# ConversorBUCK.net
KiCad netlist of a schematic drawn in EasyEDA Pro
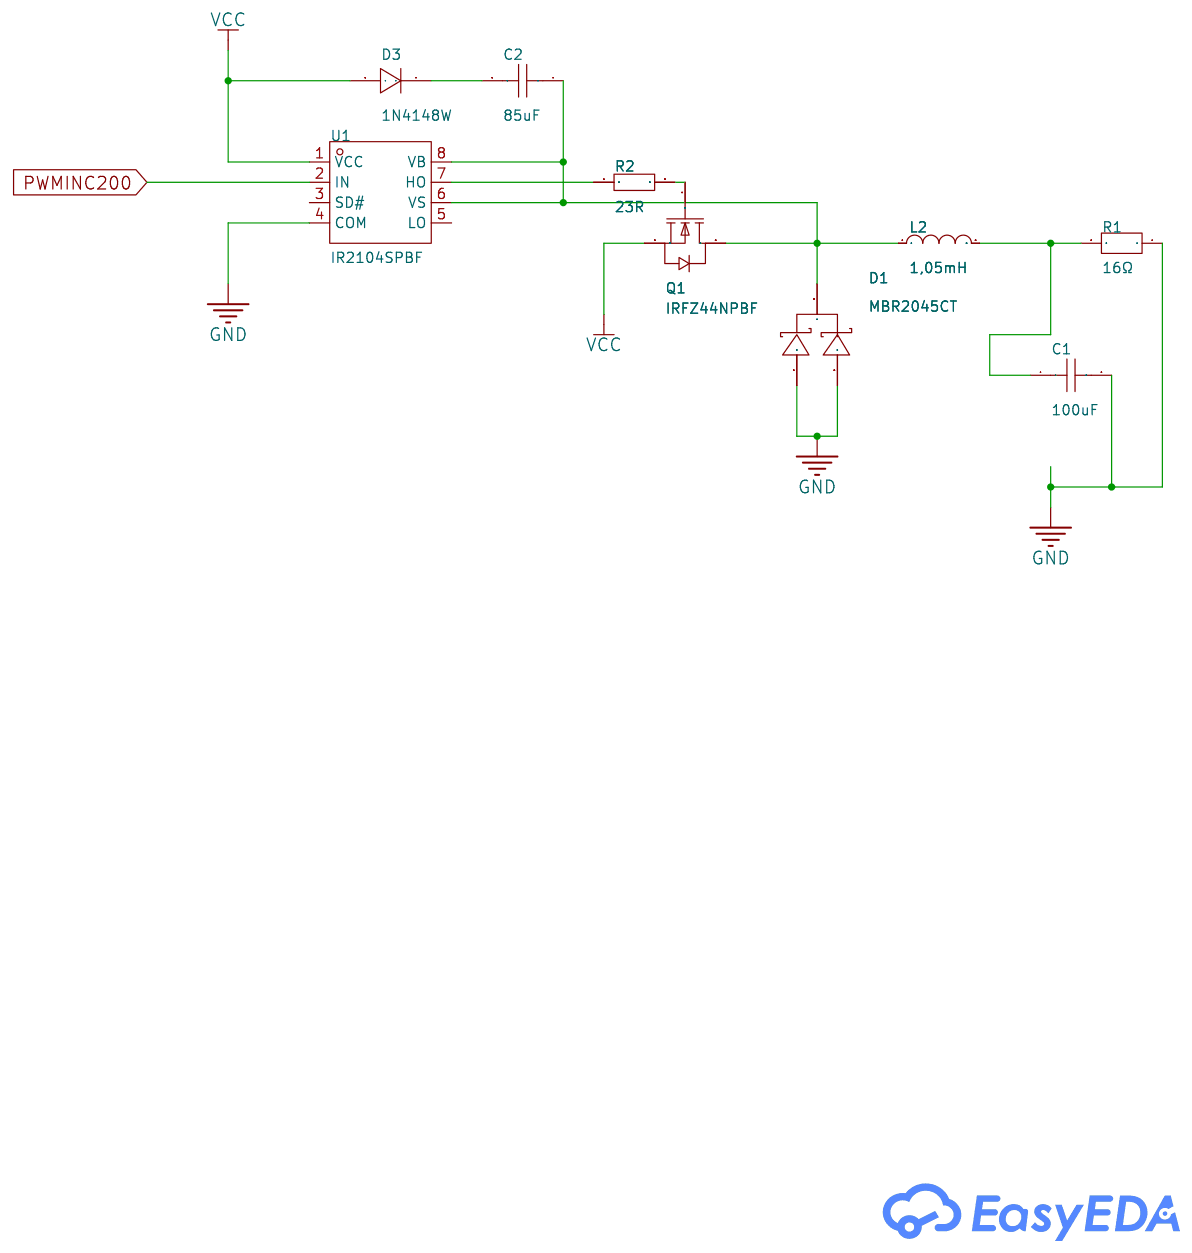
[diagram p0: schematic sheet]

(export (version "E")
  (design (tool "Eeschema 10.0.6"))
  (components
    (comp (ref "C1")
      (value "100uF")
      (footprint "easyedapro:C1210")
      (description "Capacitance:100uF Tolerance:±20% Tolerance:±20% Voltage Rating:6.3V Temperature Coefficient:X7T")
      (fields
        (field (name "Manufacturer Part") "CL32Z107MQV6PNE")
        (field (name "Manufacturer") "SAMSUNG(三星)")
      )
      (libsource (lib "easyedapro") (part "CL32Z107MQV6PNE"))
    )
    (comp (ref "C2")
      (value "85uF")
      (footprint "easyedapro:C0201")
      (libsource (lib "easyedapro") (part "CAP"))
    )
    (comp (ref "D1")
      (value "MBR2045CT")
      (footprint "easyedapro:TO-220AB-3_L10.4-W4.6-P2.54-T")
      (fields (field (name "Manufacturer") "PINGWEI(平伟)"))
      (libsource (lib "easyedapro") (part "MBR2045CT_C360496"))
    )
    (comp (ref "D3")
      (value "1N4148W")
      (footprint "easyedapro:SOD-123F_L2.7-W1.6-LS3.8-RD")
      (fields (field (name "Manufacturer") "ST(先科)"))
      (libsource (lib "easyedapro") (part "1N4148W_C81598"))
    )
    (comp (ref "L2")
      (value "1,05mH")
      (footprint "easyedapro:IND-SMD_L2.0-W1.2_PCT201210")
      (fields (field (name "Manufacturer Part") "PCT201210-1R0-M") (field (name "Manufacturer") "JIERR(捷而瑞)"))
      (libsource (lib "easyedapro") (part "PCT201210-1R0-M"))
    )
    (comp (ref "Q1")
      (value "IRFZ44NPBF")
      (footprint "easyedapro:TO-220AB-3_L10.4-W4.6-P2.54-L")
      (fields (field (name "Manufacturer") "Infineon(英飞凌)"))
      (libsource (lib "easyedapro") (part "IRFZ44NPBF_C3290502"))
    )
    (comp (ref "R1")
      (value "16Ω")
      (footprint "easyedapro:RES-TH_L20.3-W19.0-P27.00_AHA10")
      (fields (field (name "Manufacturer Part") "AHA10BJB-16R") (field (name "Manufacturer") "YAGEO(国巨)"))
      (libsource (lib "easyedapro") (part "AHA10BJB-16R"))
    )
    (comp (ref "R2") (value "23R") (footprint "easyedapro:R0402") (libsource (lib "easyedapro") (part "Res")))
    (comp (ref "U1")
      (value "IR2104SPBF")
      (footprint "easyedapro:SOIC-8_L4.9-W3.9-P1.27-LS6.0-BL")
      (fields (field (name "Manufacturer") "Infineon(英飞凌)"))
      (libsource (lib "easyedapro") (part "IR2104SPBF_C5204801"))
    )
  )
  (nets
    (net (code "1") (name "GND") (class "Default")
      (node (ref "C1") (pin "2") (pinfunction "2_2") (pintype "unspecified"))
      (node (ref "D1") (pin "1") (pinfunction "A_1") (pintype "input"))
      (node (ref "D1") (pin "3") (pinfunction "A_3") (pintype "input"))
      (node (ref "R1") (pin "1") (pinfunction "1_1") (pintype "unspecified"))
      (node (ref "U1") (pin "4") (pinfunction "COM_4") (pintype "unspecified"))
    )
    (net (code "2") (name "Net-(C1-Pad1)") (class "Default")
      (node (ref "C1") (pin "1") (pinfunction "1_1") (pintype "unspecified"))
      (node (ref "L2") (pin "2") (pinfunction "2_2") (pintype "unspecified"))
      (node (ref "R1") (pin "2") (pinfunction "2_2") (pintype "unspecified"))
    )
    (net (code "3") (name "Net-(D1-K)") (class "Default")
      (node (ref "C2") (pin "1") (pinfunction "1_1") (pintype "input"))
      (node (ref "D1") (pin "2") (pinfunction "K_2") (pintype "input"))
      (node (ref "L2") (pin "1") (pinfunction "1_1") (pintype "unspecified"))
      (node (ref "Q1") (pin "2") (pinfunction "D_2") (pintype "unspecified"))
      (node (ref "U1") (pin "6") (pinfunction "VS_6") (pintype "unspecified"))
      (node (ref "U1") (pin "8") (pinfunction "VB_8") (pintype "unspecified"))
    )
    (net (code "4") (name "Net-(D3-K)") (class "Default")
      (node (ref "C2") (pin "2") (pinfunction "2_2") (pintype "input"))
      (node (ref "D3") (pin "1") (pinfunction "K_1") (pintype "unspecified"))
    )
    (net (code "5") (name "Net-(Q1-G)") (class "Default")
      (node (ref "Q1") (pin "1") (pinfunction "G_1") (pintype "unspecified"))
      (node (ref "R2") (pin "2") (pinfunction "2_2") (pintype "input"))
    )
    (net (code "6") (name "Net-(U1-HO)") (class "Default")
      (node (ref "R2") (pin "1") (pinfunction "1_1") (pintype "input"))
      (node (ref "U1") (pin "7") (pinfunction "HO_7") (pintype "unspecified"))
    )
    (net (code "7") (name "PWMINC200") (class "Default")
      (node (ref "U1") (pin "2") (pinfunction "IN_2") (pintype "unspecified"))
    )
    (net (code "8") (name "VCC") (class "Default")
      (node (ref "D3") (pin "2") (pinfunction "A_2") (pintype "unspecified"))
      (node (ref "Q1") (pin "3") (pinfunction "S_3") (pintype "unspecified"))
      (node (ref "U1") (pin "1") (pinfunction "VCC_1") (pintype "unspecified"))
    )
    (net (code "9") (name "unconnected-(U1-LO-Pad5)") (class "Default")
      (node (ref "U1") (pin "5") (pinfunction "LO_5") (pintype "unspecified"))
    )
    (net (code "10") (name "unconnected-(U1-SD#-Pad3)") (class "Default")
      (node (ref "U1") (pin "3") (pinfunction "SD#_3") (pintype "unspecified"))
    )
  )
)
